# Encoder_RJ45.net
KiCad netlist of a schematic drawn in Altium Designer
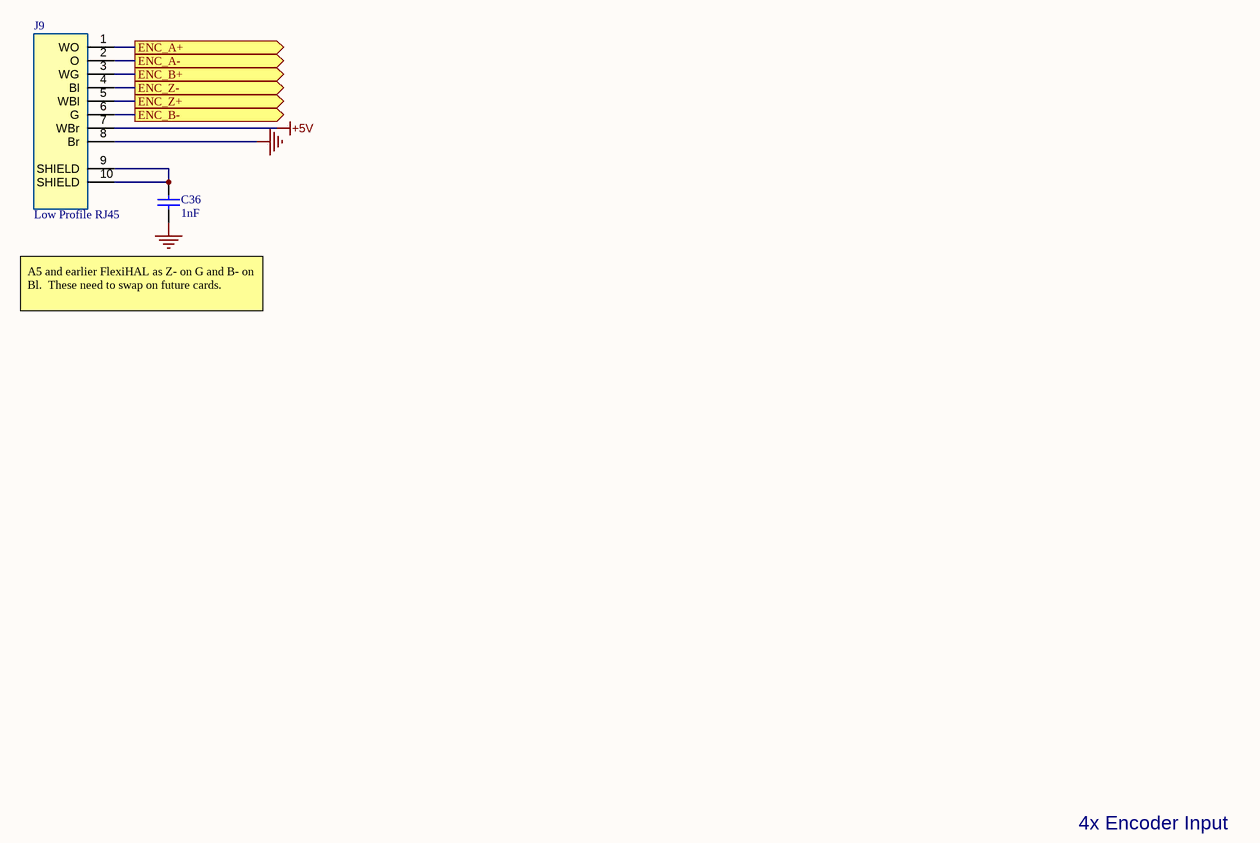
[diagram p0: Encoder_RJ45.SchDoc]

(export (version "E")
  (design (tool "Eeschema 10.0.6"))
  (components
    (comp (ref "C36")
      (value "1nF")
      (footprint "1206_C")
      (description "Chip capacitors")
      (fields
        (field (name "MANUFACTURER") "Samsung Electro-Mechanics")
        (field (name "PARTNUMBER") "CL31B102KGFNNNE")
      )
      (libsource (lib "Cap") (part "1206 1nF (102) 10% 500V"))
    )
    (comp (ref "J9")
      (value "Low Profile RJ45")
      (footprint "RJ45-SMD_MJ88-B011-HLSV6-P")
      (description "Micro USB")
      (fields (field (name "MF") "Heling"))
      (libsource (lib "Universal_CNC_Breakout") (part "MJ88-B011-HLSV6-P"))
    )
  )
  (nets
    (net (code "1") (name "+5V") (class "Default")
      (node (ref "J9") (pin "7") (pinfunction "WBr_7") (pintype "passive"))
    )
    (net (code "2") (name "/ENC_A+") (class "Default")
      (node (ref "J9") (pin "1") (pinfunction "WO_1") (pintype "passive"))
    )
    (net (code "3") (name "/ENC_A-") (class "Default")
      (node (ref "J9") (pin "2") (pinfunction "O_2") (pintype "passive"))
    )
    (net (code "4") (name "/ENC_B+") (class "Default")
      (node (ref "J9") (pin "3") (pinfunction "WG_3") (pintype "passive"))
    )
    (net (code "5") (name "/ENC_B-") (class "Default")
      (node (ref "J9") (pin "6") (pinfunction "G_6") (pintype "passive"))
    )
    (net (code "6") (name "/ENC_Z+") (class "Default")
      (node (ref "J9") (pin "5") (pinfunction "WBl_5") (pintype "passive"))
    )
    (net (code "7") (name "/ENC_Z-") (class "Default")
      (node (ref "J9") (pin "4") (pinfunction "Bl_4") (pintype "passive"))
    )
    (net (code "8") (name "GND") (class "Default")
      (node (ref "C36") (pin "1") (pinfunction "1_1") (pintype "passive"))
      (node (ref "J9") (pin "8") (pinfunction "Br_8") (pintype "passive"))
    )
    (net (code "9") (name "Net-(C36-Pad2)") (class "Default")
      (node (ref "C36") (pin "2") (pinfunction "2_2") (pintype "passive"))
      (node (ref "J9") (pin "10") (pinfunction "SHIELD_10") (pintype "passive"))
      (node (ref "J9") (pin "9") (pinfunction "SHIELD_9") (pintype "passive"))
    )
  )
)
